# Differential_Noise_Generator.net
KiCad netlist of a schematic drawn in Altium Designer
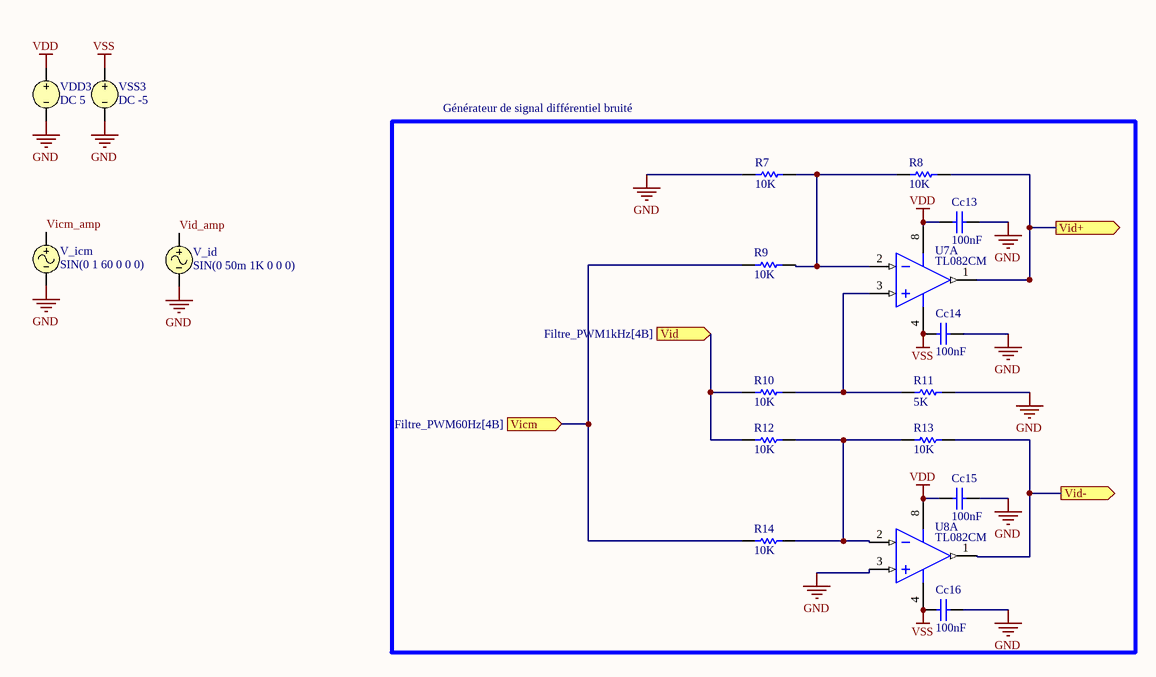
[diagram p0: Differential_Noise_Generator.SchDoc]

(export (version "E")
  (design (tool "Eeschema 10.0.6"))
  (components
    (comp (ref "Cc13")
      (value "100nF")
      (description "Capacitor")
      (libsource (lib "Simulation Generic Components") (part "Capacitor"))
    )
    (comp (ref "Cc14")
      (value "100nF")
      (description "Capacitor")
      (libsource (lib "Simulation Generic Components") (part "Capacitor"))
    )
    (comp (ref "Cc15")
      (value "100nF")
      (description "Capacitor")
      (libsource (lib "Simulation Generic Components") (part "Capacitor"))
    )
    (comp (ref "Cc16")
      (value "100nF")
      (description "Capacitor")
      (libsource (lib "Simulation Generic Components") (part "Capacitor"))
    )
    (comp (ref "R7")
      (value "10K")
      (footprint "AXIAL-0.3")
      (description "Resistor")
      (fields (field (name "Comment") "Res1") (field (name "PUBLISHER") "Altium Limited"))
      (libsource (lib "Miscellaneous Devices") (part "Res1"))
    )
    (comp (ref "R8")
      (value "10K")
      (footprint "AXIAL-0.3")
      (description "Resistor")
      (fields (field (name "Comment") "Res1") (field (name "PUBLISHER") "Altium Limited"))
      (libsource (lib "Miscellaneous Devices") (part "Res1"))
    )
    (comp (ref "R9")
      (value "10K")
      (footprint "AXIAL-0.3")
      (description "Resistor")
      (fields (field (name "Comment") "Res1") (field (name "PUBLISHER") "Altium Limited"))
      (libsource (lib "Miscellaneous Devices") (part "Res1"))
    )
    (comp (ref "R10")
      (value "10K")
      (footprint "AXIAL-0.3")
      (description "Resistor")
      (fields (field (name "Comment") "Res1") (field (name "PUBLISHER") "Altium Limited"))
      (libsource (lib "Miscellaneous Devices") (part "Res1"))
    )
    (comp (ref "R11")
      (value "5K")
      (footprint "AXIAL-0.3")
      (description "Resistor")
      (fields (field (name "Comment") "Res1") (field (name "PUBLISHER") "Altium Limited"))
      (libsource (lib "Miscellaneous Devices") (part "Res1"))
    )
    (comp (ref "R12")
      (value "10K")
      (footprint "AXIAL-0.3")
      (description "Resistor")
      (fields (field (name "Comment") "Res1") (field (name "PUBLISHER") "Altium Limited"))
      (libsource (lib "Miscellaneous Devices") (part "Res1"))
    )
    (comp (ref "R13")
      (value "10K")
      (footprint "AXIAL-0.3")
      (description "Resistor")
      (fields (field (name "Comment") "Res1") (field (name "PUBLISHER") "Altium Limited"))
      (libsource (lib "Miscellaneous Devices") (part "Res1"))
    )
    (comp (ref "R14")
      (value "10K")
      (footprint "AXIAL-0.3")
      (description "Resistor")
      (fields (field (name "Comment") "Res1") (field (name "PUBLISHER") "Altium Limited"))
      (libsource (lib "Miscellaneous Devices") (part "Res1"))
    )
    (comp (ref "U7")
      (value "TL082CM")
      (footprint "M08A_N")
      (description "Wide Bandwidth Dual JFET Input Operational Amplifier, 8-pin Narrow SOIC")
      (fields
        (field (name "MANUFACTURER") "National Semiconductor")
        (field (name "PUBLISHER") "Altium Limited")
      )
      (libsource (lib "NSC_Amplifier2026") (part "TL082CM"))
    )
    (comp (ref "U8")
      (value "TL082CM")
      (footprint "M08A_N")
      (description "Wide Bandwidth Dual JFET Input Operational Amplifier, 8-pin Narrow SOIC")
      (fields
        (field (name "MANUFACTURER") "National Semiconductor")
        (field (name "PUBLISHER") "Altium Limited")
      )
      (libsource (lib "NSC_Amplifier2026") (part "TL082CM"))
    )
    (comp (ref "VDD3")
      (value "DC 5")
      (description "Voltage Source")
      (fields (field (name "PUBLISHER") "Altium Limited"))
      (libsource (lib "Simulation Generic Components") (part "VSRC"))
    )
    (comp (ref "VSS3")
      (value "DC -5")
      (description "Voltage Source")
      (fields (field (name "PUBLISHER") "Altium Limited"))
      (libsource (lib "Simulation Generic Components") (part "VSRC"))
    )
    (comp (ref "V_icm")
      (value "SIN(0 1 60 0 0 0)")
      (description "Sinusoidal Voltage Source")
      (fields (field (name "PUBLISHER") "Altium Limited"))
      (libsource (lib "Simulation Generic Components") (part "VSIN"))
    )
    (comp (ref "V_id")
      (value "SIN(0 50m 1K 0 0 0)")
      (description "Sinusoidal Voltage Source")
      (fields (field (name "PUBLISHER") "Altium Limited"))
      (libsource (lib "Simulation Generic Components") (part "VSIN"))
    )
  )
  (nets
    (net (code "1") (name "/Vicm") (class "Default")
      (node (ref "R14") (pin "1") (pinfunction "1_1") (pintype "passive"))
      (node (ref "R9") (pin "1") (pinfunction "1_1") (pintype "passive"))
    )
    (net (code "2") (name "/Vicm_amp") (class "Default")
      (node (ref "V_icm") (pin "1") (pinfunction "1_1") (pintype "passive"))
    )
    (net (code "3") (name "/Vid") (class "Default")
      (node (ref "R10") (pin "1") (pinfunction "1_1") (pintype "passive"))
      (node (ref "R12") (pin "1") (pinfunction "1_1") (pintype "passive"))
    )
    (net (code "4") (name "/Vid+") (class "Default")
      (node (ref "R8") (pin "2") (pinfunction "2_2") (pintype "passive"))
      (node (ref "U7") (pin "1") (pinfunction "OUTA_1") (pintype "output"))
    )
    (net (code "5") (name "/Vid-") (class "Default")
      (node (ref "R13") (pin "2") (pinfunction "2_2") (pintype "passive"))
      (node (ref "U8") (pin "1") (pinfunction "OUTA_1") (pintype "output"))
    )
    (net (code "6") (name "/Vid_amp") (class "Default")
      (node (ref "V_id") (pin "1") (pinfunction "1_1") (pintype "passive"))
    )
    (net (code "7") (name "GND") (class "Default")
      (node (ref "Cc13") (pin "2") (pinfunction "2_2") (pintype "passive"))
      (node (ref "Cc14") (pin "2") (pinfunction "2_2") (pintype "passive"))
      (node (ref "Cc15") (pin "2") (pinfunction "2_2") (pintype "passive"))
      (node (ref "Cc16") (pin "2") (pinfunction "2_2") (pintype "passive"))
      (node (ref "R11") (pin "2") (pinfunction "2_2") (pintype "passive"))
      (node (ref "R7") (pin "1") (pinfunction "1_1") (pintype "passive"))
      (node (ref "U8") (pin "3") (pinfunction "INA+_3") (pintype "input"))
      (node (ref "VDD3") (pin "2") (pinfunction "2_2") (pintype "passive"))
      (node (ref "VSS3") (pin "2") (pinfunction "2_2") (pintype "passive"))
      (node (ref "V_icm") (pin "2") (pinfunction "2_2") (pintype "passive"))
      (node (ref "V_id") (pin "2") (pinfunction "2_2") (pintype "passive"))
    )
    (net (code "8") (name "Net-(U7A-INA+)") (class "Default")
      (node (ref "R10") (pin "2") (pinfunction "2_2") (pintype "passive"))
      (node (ref "R11") (pin "1") (pinfunction "1_1") (pintype "passive"))
      (node (ref "U7") (pin "3") (pinfunction "INA+_3") (pintype "input"))
    )
    (net (code "9") (name "Net-(U7A-INA-)") (class "Default")
      (node (ref "R7") (pin "2") (pinfunction "2_2") (pintype "passive"))
      (node (ref "R8") (pin "1") (pinfunction "1_1") (pintype "passive"))
      (node (ref "R9") (pin "2") (pinfunction "2_2") (pintype "passive"))
      (node (ref "U7") (pin "2") (pinfunction "INA-_2") (pintype "input"))
    )
    (net (code "10") (name "Net-(U8A-INA-)") (class "Default")
      (node (ref "R12") (pin "2") (pinfunction "2_2") (pintype "passive"))
      (node (ref "R13") (pin "1") (pinfunction "1_1") (pintype "passive"))
      (node (ref "R14") (pin "2") (pinfunction "2_2") (pintype "passive"))
      (node (ref "U8") (pin "2") (pinfunction "INA-_2") (pintype "input"))
    )
    (net (code "11") (name "VDD") (class "Default")
      (node (ref "Cc13") (pin "1") (pinfunction "1_1") (pintype "passive"))
      (node (ref "Cc15") (pin "1") (pinfunction "1_1") (pintype "passive"))
      (node (ref "U7") (pin "8") (pinfunction "V+_8") (pintype "power_in"))
      (node (ref "U8") (pin "8") (pinfunction "V+_8") (pintype "power_in"))
      (node (ref "VDD3") (pin "1") (pinfunction "1_1") (pintype "passive"))
    )
    (net (code "12") (name "VSS") (class "Default")
      (node (ref "Cc14") (pin "1") (pinfunction "1_1") (pintype "passive"))
      (node (ref "Cc16") (pin "1") (pinfunction "1_1") (pintype "passive"))
      (node (ref "U7") (pin "4") (pinfunction "V-_4") (pintype "power_in"))
      (node (ref "U8") (pin "4") (pinfunction "V-_4") (pintype "power_in"))
      (node (ref "VSS3") (pin "1") (pinfunction "1_1") (pintype "passive"))
    )
  )
)
